# CanController.net
KiCad netlist of a schematic drawn in Altium Designer
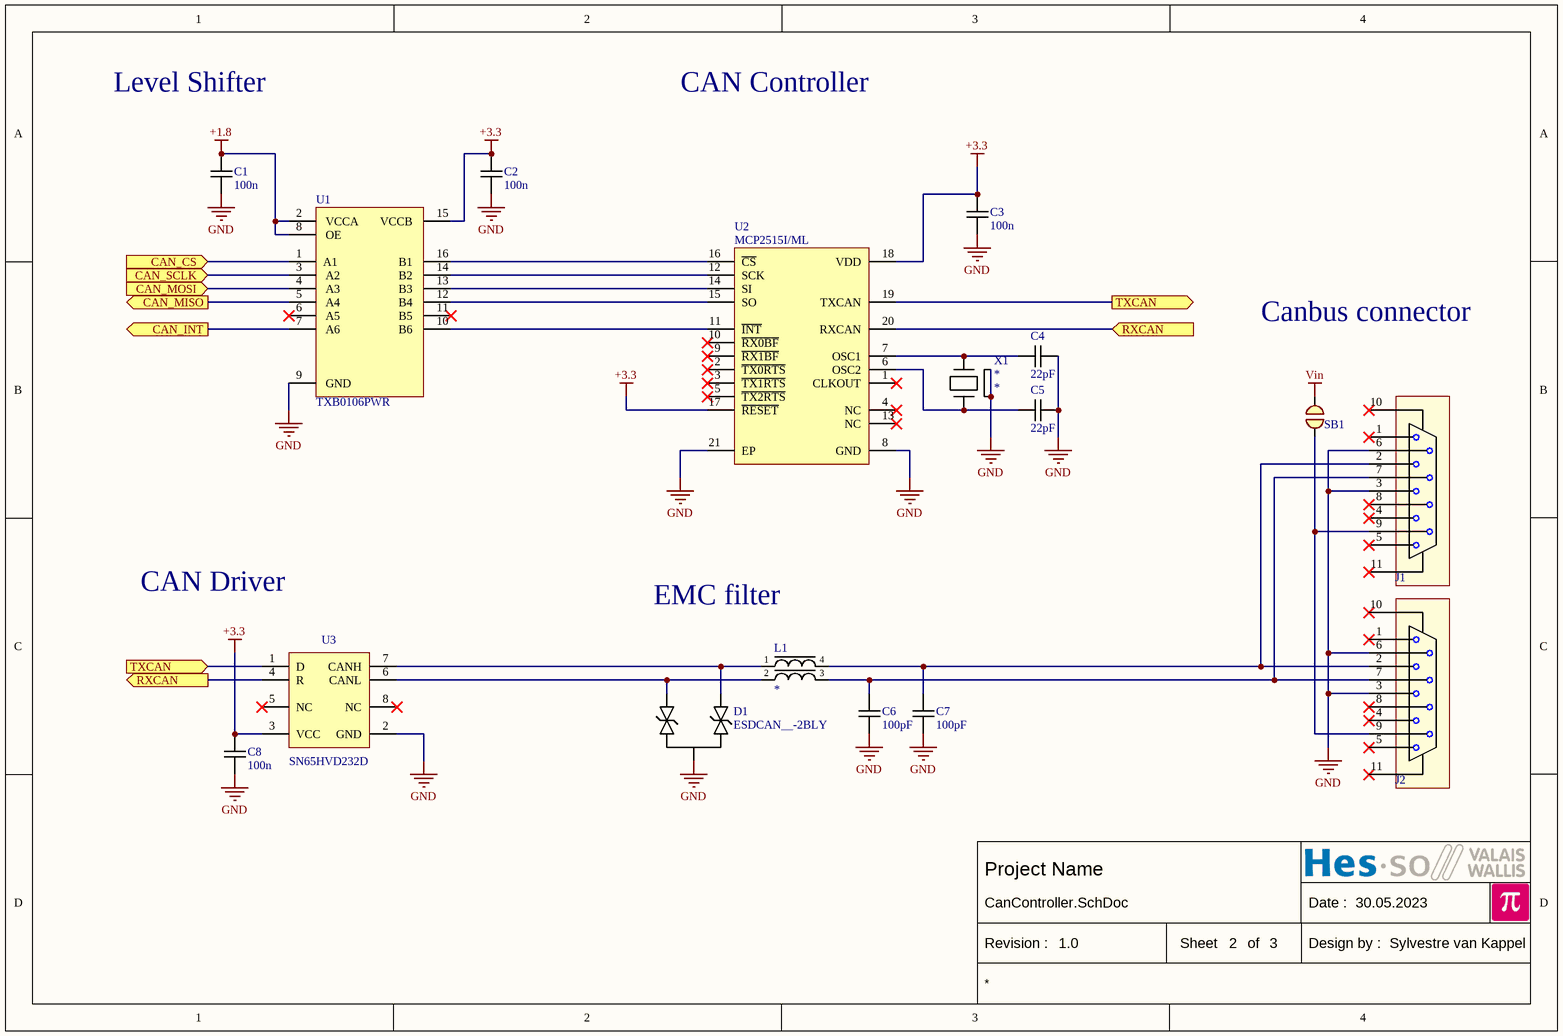
[diagram p0: CanController.SchDoc]

(export (version "E")
  (design (tool "Eeschema 10.0.6"))
  (components
    (comp (ref "C1")
      (value "100n")
      (footprint "CAPACITOR 1608 REFLOW")
      (description "Capacitor")
      (libsource (lib "Capacitor") (part "Capacitor"))
    )
    (comp (ref "C2")
      (value "100n")
      (footprint "CAPACITOR 1608 REFLOW")
      (description "Capacitor")
      (libsource (lib "Capacitor") (part "Capacitor"))
    )
    (comp (ref "C3")
      (value "100n")
      (footprint "CAPACITOR 1608 REFLOW")
      (description "Capacitor")
      (libsource (lib "Capacitor") (part "Capacitor"))
    )
    (comp (ref "C4")
      (value "22pF")
      (footprint "CAPACITOR 1608 REFLOW")
      (description "Capacitor")
      (libsource (lib "Capacitor") (part "Capacitor"))
    )
    (comp (ref "C5")
      (value "22pF")
      (footprint "CAPACITOR 1608 REFLOW")
      (description "Capacitor")
      (libsource (lib "Capacitor") (part "Capacitor"))
    )
    (comp (ref "C6")
      (value "100pF")
      (footprint "CAPACITOR 1608 REFLOW")
      (description "Capacitor")
      (libsource (lib "Capacitor") (part "Capacitor"))
    )
    (comp (ref "C7")
      (value "100pF")
      (footprint "CAPACITOR 1608 REFLOW")
      (description "Capacitor")
      (libsource (lib "Capacitor") (part "Capacitor"))
    )
    (comp (ref "C8")
      (value "100n")
      (footprint "CAPACITOR 1608 REFLOW")
      (description "Capacitor")
      (libsource (lib "Capacitor") (part "Capacitor"))
    )
    (comp (ref "D1")
      (value "ESDCAN__-2BLY")
      (footprint "SOT23 P0.95 C1.6x3.0 H1.3")
      (description "Automotive dual-line TVS diode")
      (libsource (lib "Diode") (part "Diode ESDCAN__-2BLY"))
    )
    (comp (ref "J1")
      (value "D-SUB 9 FEM GROUNDED")
      (footprint "D-SUB 9 FEM ANGLE")
      (description "D-Subminiature 9 way Socket Right Angle")
      (libsource (lib "Connector") (part "D-SUB 9 FEM GROUNDED"))
    )
    (comp (ref "J2")
      (value "D-SUB 9 FEM GROUNDED")
      (footprint "D-SUB 9 FEM ANGLE")
      (description "D-Subminiature 9 way Socket Right Angle")
      (libsource (lib "Connector") (part "D-SUB 9 FEM GROUNDED"))
    )
    (comp (ref "L1")
      (value "*")
      (footprint "L CM 2X B82793C EPCOS")
      (description "Inductor Common Mode Filter")
      (libsource (lib "Inductor") (part "L CM 2X B82793C0 EPCOS"))
    )
    (comp (ref "SB1")
      (value "*")
      (footprint "Solder Bridge 1mm Unconnected")
      (description "Solderbridge Unconnected")
      (libsource (lib "Jumper") (part "Solderbridge Unconnected"))
    )
    (comp (ref "U1")
      (value "TXB0106PWR")
      (footprint "TSSOP16 P0.65 C5.0x4.5 H1.1")
      (libsource (lib "IntegratedCircuit") (part "TXB0106PWR"))
    )
    (comp (ref "U2")
      (value "MCP2515I/ML")
      (footprint "QFN20 P0.5 T2.05x2.05 C4.0x4.0 H0.85")
      (description "Stand-Alone CAN Controller with SPI Interface")
      (libsource (lib "IntegratedCircuit") (part "MCP2515I/ML"))
    )
    (comp (ref "U3")
      (value "SN65HVD232D")
      (footprint "SO8 P1.27 C4.0X5.0 H1.75")
      (description "CAN Bus Transceiver 3V3")
      (libsource (lib "IntegratedCircuit") (part "SN65HVD232D"))
    )
    (comp (ref "X1")
      (value "*")
      (footprint "CRYSTAL C3.2x2.5 Kyocera CX3225SB")
      (description "Crystal C3.2x2.5 Kyocera CX3225SB")
      (fields (field (name "ALTIUM_VALUE") "*"))
      (libsource (lib "Oscillator") (part "Crystal C3.2x2.5 Kyocera CX3225SB"))
    )
  )
  (nets
    (net (code "1") (name "+1.8") (class "Default")
      (node (ref "C1") (pin "2") (pinfunction "2_2") (pintype "passive"))
      (node (ref "U1") (pin "2") (pinfunction "VCCA_2") (pintype "passive"))
      (node (ref "U1") (pin "8") (pinfunction "OE_8") (pintype "passive"))
    )
    (net (code "2") (name "+3.3") (class "Default")
      (node (ref "C2") (pin "2") (pinfunction "2_2") (pintype "passive"))
      (node (ref "C3") (pin "2") (pinfunction "2_2") (pintype "passive"))
      (node (ref "C8") (pin "2") (pinfunction "2_2") (pintype "passive"))
      (node (ref "U1") (pin "15") (pinfunction "VCCB_15") (pintype "passive"))
      (node (ref "U2") (pin "17") (pinfunction "~{RESET}_17") (pintype "passive"))
      (node (ref "U2") (pin "18") (pinfunction "VDD_18") (pintype "passive"))
      (node (ref "U3") (pin "3") (pinfunction "VCC_3") (pintype "passive"))
    )
    (net (code "3") (name "/CAN_CS") (class "Default")
      (node (ref "U1") (pin "1") (pinfunction "A1_1") (pintype "passive"))
    )
    (net (code "4") (name "/CAN_INT") (class "Default")
      (node (ref "U1") (pin "7") (pinfunction "A6_7") (pintype "passive"))
    )
    (net (code "5") (name "/CAN_MISO") (class "Default")
      (node (ref "U1") (pin "5") (pinfunction "A4_5") (pintype "passive"))
    )
    (net (code "6") (name "/CAN_MOSI") (class "Default")
      (node (ref "U1") (pin "4") (pinfunction "A3_4") (pintype "passive"))
    )
    (net (code "7") (name "/CAN_SCLK") (class "Default")
      (node (ref "U1") (pin "3") (pinfunction "A2_3") (pintype "passive"))
    )
    (net (code "8") (name "/RXCAN") (class "Default")
      (node (ref "U2") (pin "20") (pinfunction "RXCAN_20") (pintype "passive"))
      (node (ref "U3") (pin "4") (pinfunction "R_4") (pintype "passive"))
    )
    (net (code "9") (name "/TXCAN") (class "Default")
      (node (ref "U2") (pin "19") (pinfunction "TXCAN_19") (pintype "passive"))
      (node (ref "U3") (pin "1") (pinfunction "D_1") (pintype "passive"))
    )
    (net (code "10") (name "GND") (class "Default")
      (node (ref "C1") (pin "1") (pinfunction "1_1") (pintype "passive"))
      (node (ref "C2") (pin "1") (pinfunction "1_1") (pintype "passive"))
      (node (ref "C3") (pin "1") (pinfunction "1_1") (pintype "passive"))
      (node (ref "C4") (pin "1") (pinfunction "1_1") (pintype "passive"))
      (node (ref "C5") (pin "1") (pinfunction "1_1") (pintype "passive"))
      (node (ref "C6") (pin "1") (pinfunction "1_1") (pintype "passive"))
      (node (ref "C7") (pin "1") (pinfunction "1_1") (pintype "passive"))
      (node (ref "C8") (pin "1") (pinfunction "1_1") (pintype "passive"))
      (node (ref "D1") (pin "3") (pinfunction "COM_3") (pintype "passive"))
      (node (ref "J1") (pin "3") (pintype "passive"))
      (node (ref "J1") (pin "6") (pintype "passive"))
      (node (ref "J2") (pin "3") (pintype "passive"))
      (node (ref "J2") (pin "6") (pintype "passive"))
      (node (ref "U1") (pin "9") (pinfunction "GND_9") (pintype "passive"))
      (node (ref "U2") (pin "21") (pinfunction "EP_21") (pintype "passive"))
      (node (ref "U2") (pin "8") (pinfunction "GND_8") (pintype "passive"))
      (node (ref "U3") (pin "2") (pinfunction "GND_2") (pintype "passive"))
      (node (ref "X1") (pin "2") (pinfunction "2_2") (pintype "passive"))
      (node (ref "X1") (pin "4") (pinfunction "4_4") (pintype "passive"))
    )
    (net (code "11") (name "Net-(C6-Pad2)") (class "Default")
      (node (ref "C6") (pin "2") (pinfunction "2_2") (pintype "passive"))
      (node (ref "J1") (pin "7") (pintype "passive"))
      (node (ref "J2") (pin "7") (pintype "passive"))
      (node (ref "L1") (pin "3") (pinfunction "3_3") (pintype "passive"))
    )
    (net (code "12") (name "Net-(C7-Pad2)") (class "Default")
      (node (ref "C7") (pin "2") (pinfunction "2_2") (pintype "passive"))
      (node (ref "J1") (pin "2") (pintype "passive"))
      (node (ref "J2") (pin "2") (pintype "passive"))
      (node (ref "L1") (pin "4") (pinfunction "4_4") (pintype "passive"))
    )
    (net (code "13") (name "Net-(D1-A1)") (class "Default")
      (node (ref "D1") (pin "1") (pinfunction "A1_1") (pintype "passive"))
      (node (ref "L1") (pin "1") (pinfunction "1_1") (pintype "passive"))
      (node (ref "U3") (pin "7") (pinfunction "CANH_7") (pintype "passive"))
    )
    (net (code "14") (name "Net-(D1-C2)") (class "Default")
      (node (ref "D1") (pin "2") (pinfunction "C2_2") (pintype "passive"))
      (node (ref "L1") (pin "2") (pinfunction "2_2") (pintype "passive"))
      (node (ref "U3") (pin "6") (pinfunction "CANL_6") (pintype "passive"))
    )
    (net (code "15") (name "Net-(SB1-1)") (class "Default")
      (node (ref "J1") (pin "9") (pintype "passive"))
      (node (ref "J2") (pin "9") (pintype "passive"))
      (node (ref "SB1") (pin "2") (pinfunction "1_2") (pintype "passive"))
    )
    (net (code "16") (name "Net-(U1-B1)") (class "Default")
      (node (ref "U1") (pin "16") (pinfunction "B1_16") (pintype "passive"))
      (node (ref "U2") (pin "16") (pinfunction "~{CS}_16") (pintype "passive"))
    )
    (net (code "17") (name "Net-(U1-B2)") (class "Default")
      (node (ref "U1") (pin "14") (pinfunction "B2_14") (pintype "passive"))
      (node (ref "U2") (pin "12") (pinfunction "SCK_12") (pintype "passive"))
    )
    (net (code "18") (name "Net-(U1-B3)") (class "Default")
      (node (ref "U1") (pin "13") (pinfunction "B3_13") (pintype "passive"))
      (node (ref "U2") (pin "14") (pinfunction "SI_14") (pintype "passive"))
    )
    (net (code "19") (name "Net-(U1-B4)") (class "Default")
      (node (ref "U1") (pin "12") (pinfunction "B4_12") (pintype "passive"))
      (node (ref "U2") (pin "15") (pinfunction "SO_15") (pintype "passive"))
    )
    (net (code "20") (name "Net-(U1-B6)") (class "Default")
      (node (ref "U1") (pin "10") (pinfunction "B6_10") (pintype "passive"))
      (node (ref "U2") (pin "11") (pinfunction "~{INT}_11") (pintype "passive"))
    )
    (net (code "21") (name "Net-(U2-OSC1)") (class "Default")
      (node (ref "C4") (pin "2") (pinfunction "2_2") (pintype "passive"))
      (node (ref "U2") (pin "7") (pinfunction "OSC1_7") (pintype "passive"))
      (node (ref "X1") (pin "3") (pinfunction "3_3") (pintype "passive"))
    )
    (net (code "22") (name "Net-(U2-OSC2)") (class "Default")
      (node (ref "C5") (pin "2") (pinfunction "2_2") (pintype "passive"))
      (node (ref "U2") (pin "6") (pinfunction "OSC2_6") (pintype "passive"))
      (node (ref "X1") (pin "1") (pinfunction "1_1") (pintype "passive"))
    )
    (net (code "23") (name "Vin") (class "Default")
      (node (ref "SB1") (pin "1") (pinfunction "0_1") (pintype "passive"))
    )
    (net (code "24") (name "unconnected-(J1-Pad1)") (class "Default")
      (node (ref "J1") (pin "1") (pintype "passive+no_connect"))
    )
    (net (code "25") (name "unconnected-(J1-Pad4)") (class "Default")
      (node (ref "J1") (pin "4") (pintype "passive+no_connect"))
    )
    (net (code "26") (name "unconnected-(J1-Pad5)") (class "Default")
      (node (ref "J1") (pin "5") (pintype "passive+no_connect"))
    )
    (net (code "27") (name "unconnected-(J1-Pad8)") (class "Default")
      (node (ref "J1") (pin "8") (pintype "passive+no_connect"))
    )
    (net (code "28") (name "unconnected-(J1-Pad10)") (class "Default")
      (node (ref "J1") (pin "10") (pintype "passive+no_connect"))
    )
    (net (code "29") (name "unconnected-(J1-Pad11)") (class "Default")
      (node (ref "J1") (pin "11") (pintype "passive+no_connect"))
    )
    (net (code "30") (name "unconnected-(J2-Pad1)") (class "Default")
      (node (ref "J2") (pin "1") (pintype "passive+no_connect"))
    )
    (net (code "31") (name "unconnected-(J2-Pad4)") (class "Default")
      (node (ref "J2") (pin "4") (pintype "passive+no_connect"))
    )
    (net (code "32") (name "unconnected-(J2-Pad5)") (class "Default")
      (node (ref "J2") (pin "5") (pintype "passive+no_connect"))
    )
    (net (code "33") (name "unconnected-(J2-Pad8)") (class "Default")
      (node (ref "J2") (pin "8") (pintype "passive+no_connect"))
    )
    (net (code "34") (name "unconnected-(J2-Pad10)") (class "Default")
      (node (ref "J2") (pin "10") (pintype "passive+no_connect"))
    )
    (net (code "35") (name "unconnected-(J2-Pad11)") (class "Default")
      (node (ref "J2") (pin "11") (pintype "passive+no_connect"))
    )
    (net (code "36") (name "unconnected-(U1-A5-Pad6)") (class "Default")
      (node (ref "U1") (pin "6") (pinfunction "A5_6") (pintype "passive+no_connect"))
    )
    (net (code "37") (name "unconnected-(U1-B5-Pad11)") (class "Default")
      (node (ref "U1") (pin "11") (pinfunction "B5_11") (pintype "passive+no_connect"))
    )
    (net (code "38") (name "unconnected-(U2-CLKOUT-Pad1)") (class "Default")
      (node (ref "U2") (pin "1") (pinfunction "CLKOUT_1") (pintype "passive+no_connect"))
    )
    (net (code "39") (name "unconnected-(U2-NC-Pad4)") (class "Default")
      (node (ref "U2") (pin "4") (pinfunction "NC_4") (pintype "passive+no_connect"))
    )
    (net (code "40") (name "unconnected-(U2-NC-Pad13)") (class "Default")
      (node (ref "U2") (pin "13") (pinfunction "NC_13") (pintype "passive+no_connect"))
    )
    (net (code "41") (name "unconnected-(U2-~{RX0BF}-Pad10)") (class "Default")
      (node (ref "U2") (pin "10") (pinfunction "~{RX0BF}_10") (pintype "passive+no_connect"))
    )
    (net (code "42") (name "unconnected-(U2-~{RX1BF}-Pad9)") (class "Default")
      (node (ref "U2") (pin "9") (pinfunction "~{RX1BF}_9") (pintype "passive+no_connect"))
    )
    (net (code "43") (name "unconnected-(U2-~{TX0RTS}-Pad2)") (class "Default")
      (node (ref "U2") (pin "2") (pinfunction "~{TX0RTS}_2") (pintype "passive+no_connect"))
    )
    (net (code "44") (name "unconnected-(U2-~{TX1RTS}-Pad3)") (class "Default")
      (node (ref "U2") (pin "3") (pinfunction "~{TX1RTS}_3") (pintype "passive+no_connect"))
    )
    (net (code "45") (name "unconnected-(U2-~{TX2RTS}-Pad5)") (class "Default")
      (node (ref "U2") (pin "5") (pinfunction "~{TX2RTS}_5") (pintype "passive+no_connect"))
    )
    (net (code "46") (name "unconnected-(U3-NC-Pad5)") (class "Default")
      (node (ref "U3") (pin "5") (pinfunction "NC_5") (pintype "passive+no_connect"))
    )
    (net (code "47") (name "unconnected-(U3-NC-Pad8)") (class "Default")
      (node (ref "U3") (pin "8") (pinfunction "NC_8") (pintype "passive+no_connect"))
    )
  )
)
